# pll.net
KiCad netlist of a schematic drawn in EAGLE
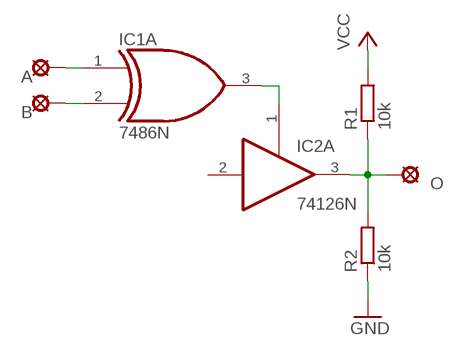
[diagram p0: schematic, sheet 1]

(export (version "E")
  (design (tool "Eeschema 10.0.6"))
  (components
    (comp (ref "A")
      (value "LSP11")
      (footprint "eagle-import:LSP11")
      (libsource (lib "eagle-import") (part "LSP11"))
    )
    (comp (ref "B")
      (value "LSP11")
      (footprint "eagle-import:LSP11")
      (libsource (lib "eagle-import") (part "LSP11"))
    )
    (comp (ref "IC1")
      (value "7486N")
      (footprint "eagle-import:DIL14")
      (libsource (lib "eagle-import") (part "7486N"))
    )
    (comp (ref "IC2")
      (value "74126N")
      (footprint "eagle-import:DIL14")
      (libsource (lib "eagle-import") (part "74126N"))
    )
    (comp (ref "O")
      (value "LSP11")
      (footprint "eagle-import:LSP11")
      (libsource (lib "eagle-import") (part "LSP11"))
    )
    (comp (ref "R1")
      (value "10k")
      (footprint "eagle-import:0204_7")
      (libsource (lib "eagle-import") (part "R-EU_0204/7"))
    )
    (comp (ref "R2")
      (value "10k")
      (footprint "eagle-import:0204_7")
      (libsource (lib "eagle-import") (part "R-EU_0204/7"))
    )
  )
  (nets
    (net (code "1") (name "GND") (class "Default")
      (node (ref "R2") (pin "1") (pinfunction "1_1") (pintype "passive"))
    )
    (net (code "2") (name "Net-(IC1A-I0)") (class "Default")
      (node (ref "A") (pin "MP") (pinfunction "MP_MP") (pintype "passive"))
      (node (ref "IC1") (pin "1") (pinfunction "I0_1") (pintype "input"))
    )
    (net (code "3") (name "Net-(IC1A-I1)") (class "Default")
      (node (ref "B") (pin "MP") (pinfunction "MP_MP") (pintype "passive"))
      (node (ref "IC1") (pin "2") (pinfunction "I1_2") (pintype "input"))
    )
    (net (code "4") (name "Net-(IC1A-O)") (class "Default")
      (node (ref "IC1") (pin "3") (pinfunction "O_3") (pintype "output"))
      (node (ref "IC2") (pin "1") (pinfunction "OE_1") (pintype "input"))
    )
    (net (code "5") (name "Net-(IC2A-O)") (class "Default")
      (node (ref "IC2") (pin "3") (pinfunction "O_3") (pintype "output"))
      (node (ref "O") (pin "MP") (pinfunction "MP_MP") (pintype "passive"))
      (node (ref "R1") (pin "1") (pinfunction "1_1") (pintype "passive"))
      (node (ref "R2") (pin "2") (pinfunction "2_2") (pintype "passive"))
    )
    (net (code "6") (name "VCC") (class "Default")
      (node (ref "R1") (pin "2") (pinfunction "2_2") (pintype "passive"))
    )
    (net (code "7") (name "unconnected-(IC2A-I-Pad2)") (class "Default")
      (node (ref "IC2") (pin "2") (pinfunction "I_2") (pintype "input"))
    )
  )
)
